# tlv61220.net
KiCad netlist of a schematic drawn in EAGLE
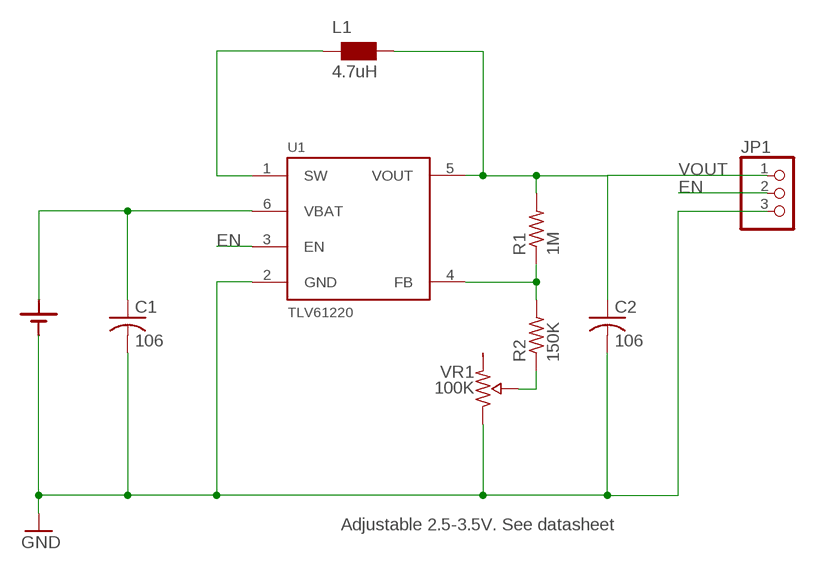
[diagram p0: schematic, sheet 1]

(export (version "E")
  (design (tool "Eeschema 10.0.6"))
  (components
    (comp (ref "C1")
      (value "106")
      (footprint "eagle-import:1206")
      (libsource (lib "eagle-import") (part "C-1206"))
    )
    (comp (ref "C2")
      (value "106")
      (footprint "eagle-import:1206")
      (libsource (lib "eagle-import") (part "C-1206"))
    )
    (comp (ref "JP1")
      (value "PINHD-1X03_2.54-S")
      (footprint "eagle-import:1X03-S")
      (libsource (lib "eagle-import") (part "PINHD-1X03_2.54-S"))
    )
    (comp (ref "L1")
      (value "4.7uH")
      (footprint "eagle-import:WE-KI_0805_B")
      (libsource (lib "eagle-import") (part "WE-KI_0805_B"))
    )
    (comp (ref "R1")
      (value "1M")
      (footprint "eagle-import:0603")
      (libsource (lib "eagle-import") (part "R0603"))
    )
    (comp (ref "R2")
      (value "150K")
      (footprint "eagle-import:0603")
      (libsource (lib "eagle-import") (part "R0603"))
    )
    (comp (ref "U$1")
      (value "LR44_PTH")
      (footprint "eagle-import:LR44")
      (libsource (lib "eagle-import") (part "LR44_PTH"))
    )
    (comp (ref "U1")
      (value "TLV61220")
      (footprint "eagle-import:SOT23-6")
      (libsource (lib "eagle-import") (part "TLV61220"))
    )
    (comp (ref "VR1")
      (value "100K")
      (footprint "eagle-import:POT_0.2X0.25")
      (libsource (lib "eagle-import") (part "TRIM-2X2.5"))
    )
  )
  (nets
    (net (code "1") (name "/EN") (class "Default")
      (node (ref "JP1") (pin "2") (pinfunction "2_2") (pintype "passive"))
      (node (ref "U1") (pin "3") (pinfunction "EN_3") (pintype "bidirectional"))
    )
    (net (code "2") (name "/VOUT") (class "Default")
      (node (ref "C2") (pin "1") (pinfunction "+_1") (pintype "passive"))
      (node (ref "JP1") (pin "1") (pinfunction "1_1") (pintype "passive"))
      (node (ref "L1") (pin "1") (pinfunction "2_1") (pintype "passive"))
      (node (ref "R1") (pin "2") (pinfunction "2_2") (pintype "passive"))
      (node (ref "U1") (pin "5") (pinfunction "VOUT_5") (pintype "bidirectional"))
    )
    (net (code "3") (name "GND") (class "Default")
      (node (ref "C1") (pin "2") (pinfunction "-_2") (pintype "passive"))
      (node (ref "C2") (pin "2") (pinfunction "-_2") (pintype "passive"))
      (node (ref "JP1") (pin "3") (pinfunction "3_3") (pintype "passive"))
      (node (ref "U$1") (pin "GND") (pinfunction "-_GND") (pintype "passive"))
      (node (ref "U1") (pin "2") (pinfunction "GND_2") (pintype "bidirectional"))
      (node (ref "VR1") (pin "A") (pinfunction "A_A") (pintype "passive"))
    )
    (net (code "4") (name "Net-(C1-+)") (class "Default")
      (node (ref "C1") (pin "1") (pinfunction "+_1") (pintype "passive"))
      (node (ref "U$1") (pin "+1") (pinfunction "+_+1") (pintype "passive"))
      (node (ref "U$1") (pin "+2") (pinfunction "+_+2") (pintype "passive"))
      (node (ref "U1") (pin "6") (pinfunction "VBAT_6") (pintype "bidirectional"))
    )
    (net (code "5") (name "Net-(L1-1)") (class "Default")
      (node (ref "L1") (pin "2") (pinfunction "1_2") (pintype "passive"))
      (node (ref "U1") (pin "1") (pinfunction "SW_1") (pintype "bidirectional"))
    )
    (net (code "6") (name "Net-(U1-FB)") (class "Default")
      (node (ref "R1") (pin "1") (pinfunction "1_1") (pintype "passive"))
      (node (ref "R2") (pin "2") (pinfunction "2_2") (pintype "passive"))
      (node (ref "U1") (pin "4") (pinfunction "FB_4") (pintype "bidirectional"))
    )
    (net (code "7") (name "Net-(VR1-WIPER)") (class "Default")
      (node (ref "R2") (pin "1") (pinfunction "1_1") (pintype "passive"))
      (node (ref "VR1") (pin "W") (pinfunction "WIPER_W") (pintype "passive"))
    )
    (net (code "8") (name "unconnected-(VR1-PadB)") (class "Default")
      (node (ref "VR1") (pin "B") (pinfunction "B_B") (pintype "passive"))
    )
  )
)
